# Sensor-BMP280.net
KiCad netlist of a schematic drawn in EAGLE
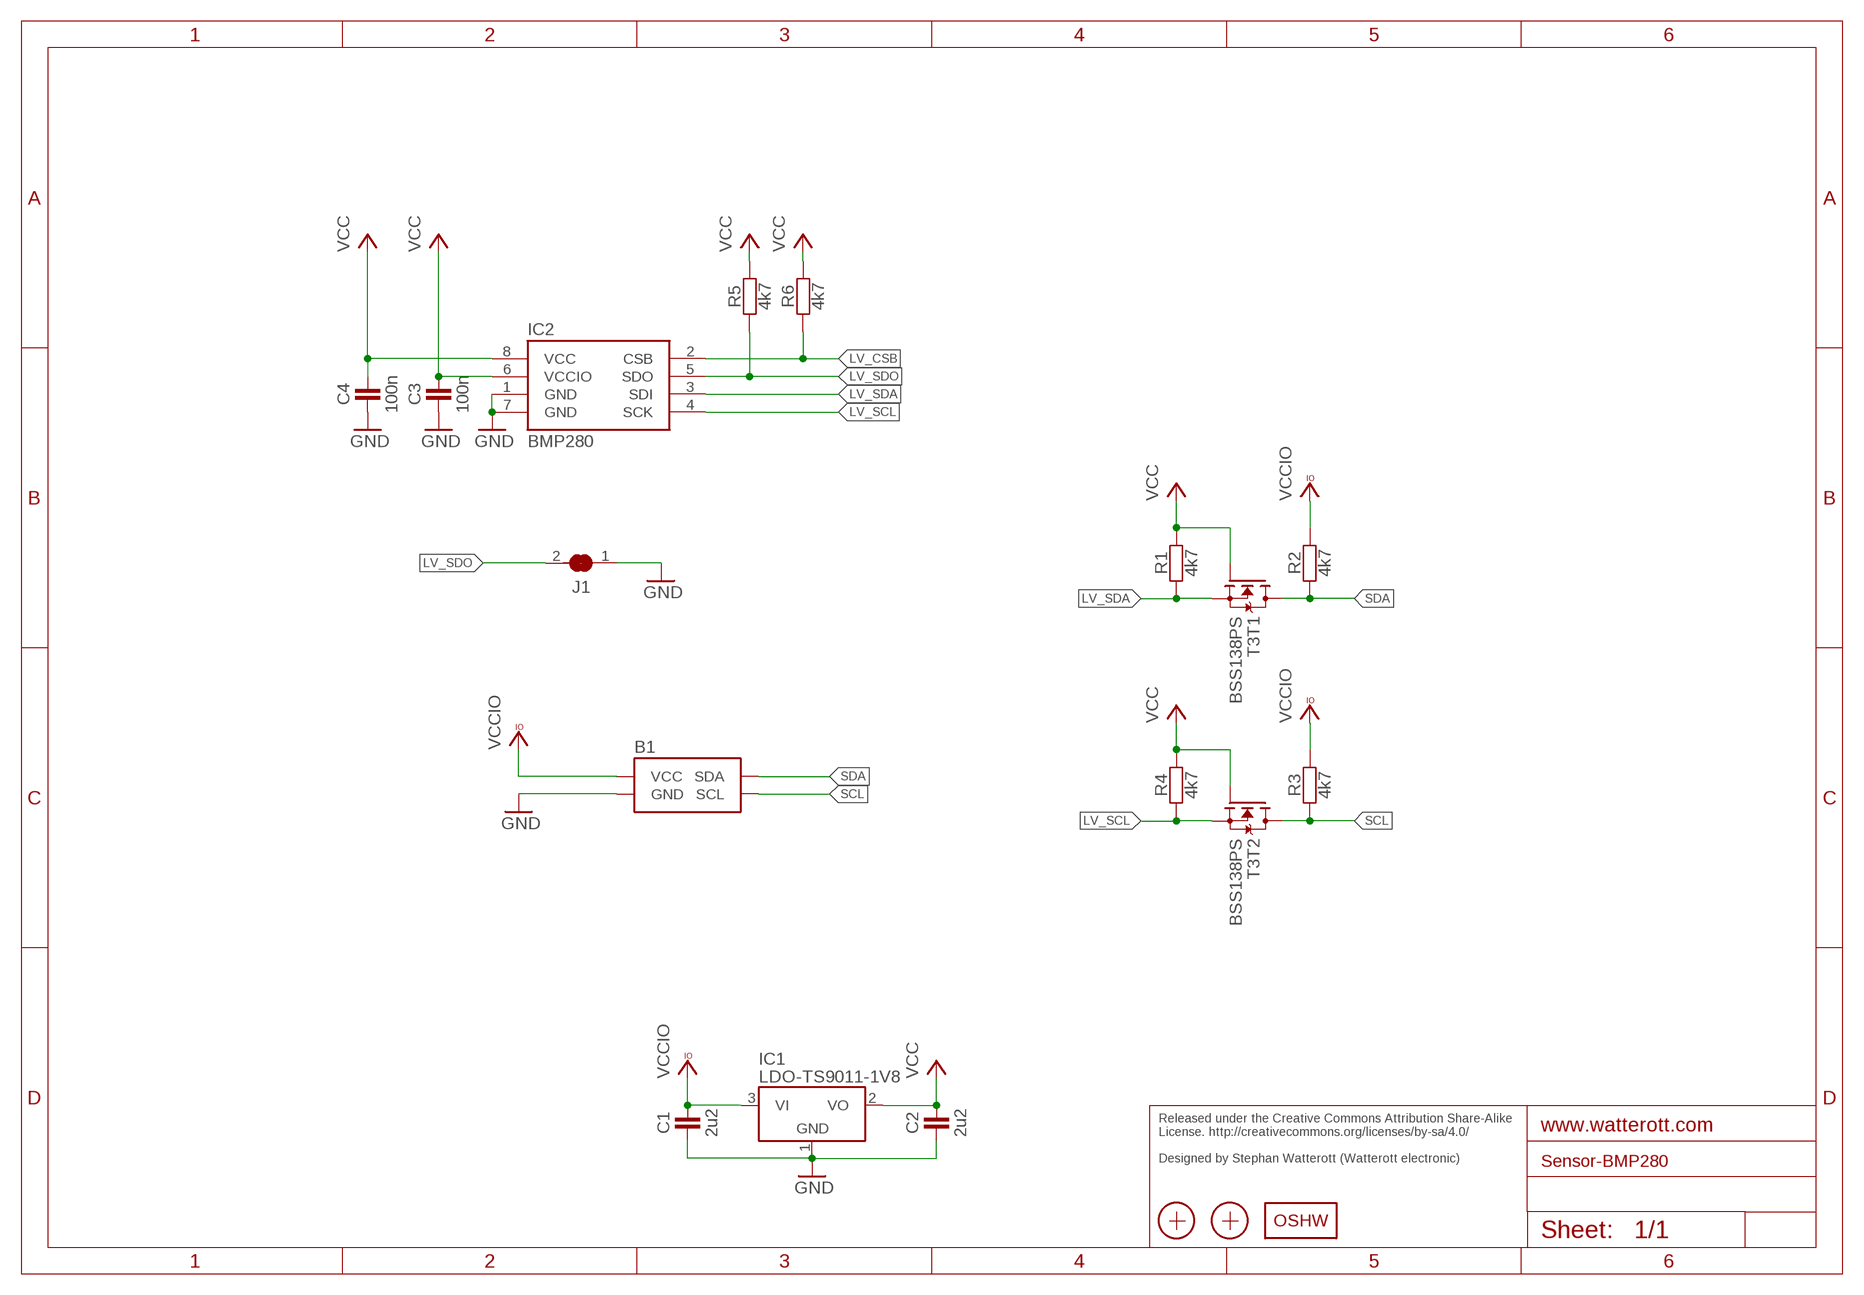
[diagram p0: schematic, sheet 1]

(export (version "E")
  (design (tool "Eeschema 10.0.6"))
  (components
    (comp (ref "B1")
      (value "SENSEBOX_I2C")
      (footprint "eagle-import:SENSEBOX_I2C")
      (libsource (lib "eagle-import") (part "SENSEBOX_I2C"))
    )
    (comp (ref "C1")
      (value "2u2")
      (footprint "eagle-import:C0402")
      (libsource (lib "eagle-import") (part "CAPACITOR-0402"))
    )
    (comp (ref "C2")
      (value "2u2")
      (footprint "eagle-import:C0402")
      (libsource (lib "eagle-import") (part "CAPACITOR-0402"))
    )
    (comp (ref "C3")
      (value "100n")
      (footprint "eagle-import:C0402")
      (libsource (lib "eagle-import") (part "CAPACITOR-0402"))
    )
    (comp (ref "C4")
      (value "100n")
      (footprint "eagle-import:C0402")
      (libsource (lib "eagle-import") (part "CAPACITOR-0402"))
    )
    (comp (ref "IC1")
      (value "LDO-TS9011-1V8")
      (footprint "eagle-import:SOT23")
      (libsource (lib "eagle-import") (part "LDO-TS9011-3V3"))
    )
    (comp (ref "IC2")
      (value "BMP280")
      (footprint "eagle-import:LGA8")
      (libsource (lib "eagle-import") (part "BMP280"))
    )
    (comp (ref "J1")
      (value "JUMPER2-0402-NC")
      (footprint "eagle-import:JUMPER2-0402_NC")
      (libsource (lib "eagle-import") (part "JUMPER2-0402-NC"))
    )
    (comp (ref "LOGO2")
      (value "OSHW_LOGOX0070")
      (footprint "eagle-import:OSHW_6X70")
      (libsource (lib "eagle-import") (part "OSHW_LOGOX0070"))
    )
    (comp (ref "R1")
      (value "4k7")
      (footprint "eagle-import:C0402")
      (libsource (lib "eagle-import") (part "RESISTOR-0402"))
    )
    (comp (ref "R2")
      (value "4k7")
      (footprint "eagle-import:C0402")
      (libsource (lib "eagle-import") (part "RESISTOR-0402"))
    )
    (comp (ref "R3")
      (value "4k7")
      (footprint "eagle-import:C0402")
      (libsource (lib "eagle-import") (part "RESISTOR-0402"))
    )
    (comp (ref "R4")
      (value "4k7")
      (footprint "eagle-import:C0402")
      (libsource (lib "eagle-import") (part "RESISTOR-0402"))
    )
    (comp (ref "R5")
      (value "4k7")
      (footprint "eagle-import:C0402")
      (libsource (lib "eagle-import") (part "RESISTOR-0402"))
    )
    (comp (ref "R6")
      (value "4k7")
      (footprint "eagle-import:C0402")
      (libsource (lib "eagle-import") (part "RESISTOR-0402"))
    )
    (comp (ref "T3")
      (value "BSS138PS")
      (footprint "eagle-import:SOT363")
      (libsource (lib "eagle-import") (part "BSS138PS"))
    )
    (comp (ref "X1")
      (value "PASSER-07")
      (footprint "eagle-import:PASSER_07MM")
      (libsource (lib "eagle-import") (part "PASSER-07"))
    )
    (comp (ref "X2")
      (value "PASSER-07")
      (footprint "eagle-import:PASSER_07MM")
      (libsource (lib "eagle-import") (part "PASSER-07"))
    )
  )
  (nets
    (net (code "1") (name "GND") (class "Default")
      (node (ref "B1") (pin "GND") (pinfunction "GND_GND") (pintype "power_in"))
      (node (ref "C1") (pin "1") (pinfunction "1_1") (pintype "passive"))
      (node (ref "C2") (pin "1") (pinfunction "1_1") (pintype "passive"))
      (node (ref "C3") (pin "1") (pinfunction "1_1") (pintype "passive"))
      (node (ref "C4") (pin "1") (pinfunction "1_1") (pintype "passive"))
      (node (ref "IC1") (pin "1") (pinfunction "GND_1") (pintype "passive"))
      (node (ref "IC2") (pin "1") (pinfunction "GND_1") (pintype "power_in"))
      (node (ref "IC2") (pin "7") (pinfunction "GND_7") (pintype "power_in"))
      (node (ref "J1") (pin "1") (pinfunction "1_1") (pintype "passive"))
    )
    (net (code "2") (name "LV_CSB") (class "Default")
      (node (ref "IC2") (pin "2") (pinfunction "CSB_2") (pintype "input"))
      (node (ref "R6") (pin "1") (pinfunction "1_1") (pintype "passive"))
    )
    (net (code "3") (name "LV_SCL") (class "Default")
      (node (ref "IC2") (pin "4") (pinfunction "SCK_4") (pintype "bidirectional"))
      (node (ref "R4") (pin "1") (pinfunction "1_1") (pintype "passive"))
      (node (ref "T3") (pin "4") (pinfunction "S_4") (pintype "passive"))
    )
    (net (code "4") (name "LV_SDA") (class "Default")
      (node (ref "IC2") (pin "3") (pinfunction "SDI_3") (pintype "bidirectional"))
      (node (ref "R1") (pin "1") (pinfunction "1_1") (pintype "passive"))
      (node (ref "T3") (pin "1") (pinfunction "S_1") (pintype "passive"))
    )
    (net (code "5") (name "LV_SDO") (class "Default")
      (node (ref "IC2") (pin "5") (pinfunction "SDO_5") (pintype "bidirectional"))
      (node (ref "J1") (pin "2") (pinfunction "2_2") (pintype "passive"))
      (node (ref "R5") (pin "1") (pinfunction "1_1") (pintype "passive"))
    )
    (net (code "6") (name "SCL") (class "Default")
      (node (ref "B1") (pin "SCL") (pinfunction "SCL_SCL") (pintype "bidirectional"))
      (node (ref "R3") (pin "1") (pinfunction "1_1") (pintype "passive"))
      (node (ref "T3") (pin "3") (pinfunction "D_3") (pintype "passive"))
    )
    (net (code "7") (name "SDA") (class "Default")
      (node (ref "B1") (pin "SDA") (pinfunction "SDA_SDA") (pintype "bidirectional"))
      (node (ref "R2") (pin "1") (pinfunction "1_1") (pintype "passive"))
      (node (ref "T3") (pin "6") (pinfunction "D_6") (pintype "passive"))
    )
    (net (code "8") (name "VCC") (class "Default")
      (node (ref "C2") (pin "2") (pinfunction "2_2") (pintype "passive"))
      (node (ref "C3") (pin "2") (pinfunction "2_2") (pintype "passive"))
      (node (ref "C4") (pin "2") (pinfunction "2_2") (pintype "passive"))
      (node (ref "IC1") (pin "2") (pinfunction "VO_2") (pintype "passive"))
      (node (ref "IC2") (pin "6") (pinfunction "VCCIO_6") (pintype "power_in"))
      (node (ref "IC2") (pin "8") (pinfunction "VCC_8") (pintype "power_in"))
      (node (ref "R1") (pin "2") (pinfunction "2_2") (pintype "passive"))
      (node (ref "R4") (pin "2") (pinfunction "2_2") (pintype "passive"))
      (node (ref "R5") (pin "2") (pinfunction "2_2") (pintype "passive"))
      (node (ref "R6") (pin "2") (pinfunction "2_2") (pintype "passive"))
      (node (ref "T3") (pin "2") (pinfunction "G_2") (pintype "passive"))
      (node (ref "T3") (pin "5") (pinfunction "G_5") (pintype "passive"))
    )
    (net (code "9") (name "VCCIO") (class "Default")
      (node (ref "B1") (pin "VCC") (pinfunction "VCC_VCC") (pintype "power_in"))
      (node (ref "C1") (pin "2") (pinfunction "2_2") (pintype "passive"))
      (node (ref "IC1") (pin "3") (pinfunction "VI_3") (pintype "input"))
      (node (ref "R2") (pin "2") (pinfunction "2_2") (pintype "passive"))
      (node (ref "R3") (pin "2") (pinfunction "2_2") (pintype "passive"))
    )
  )
)
